# joystick_if.net
KiCad netlist of a schematic drawn in Altium Designer
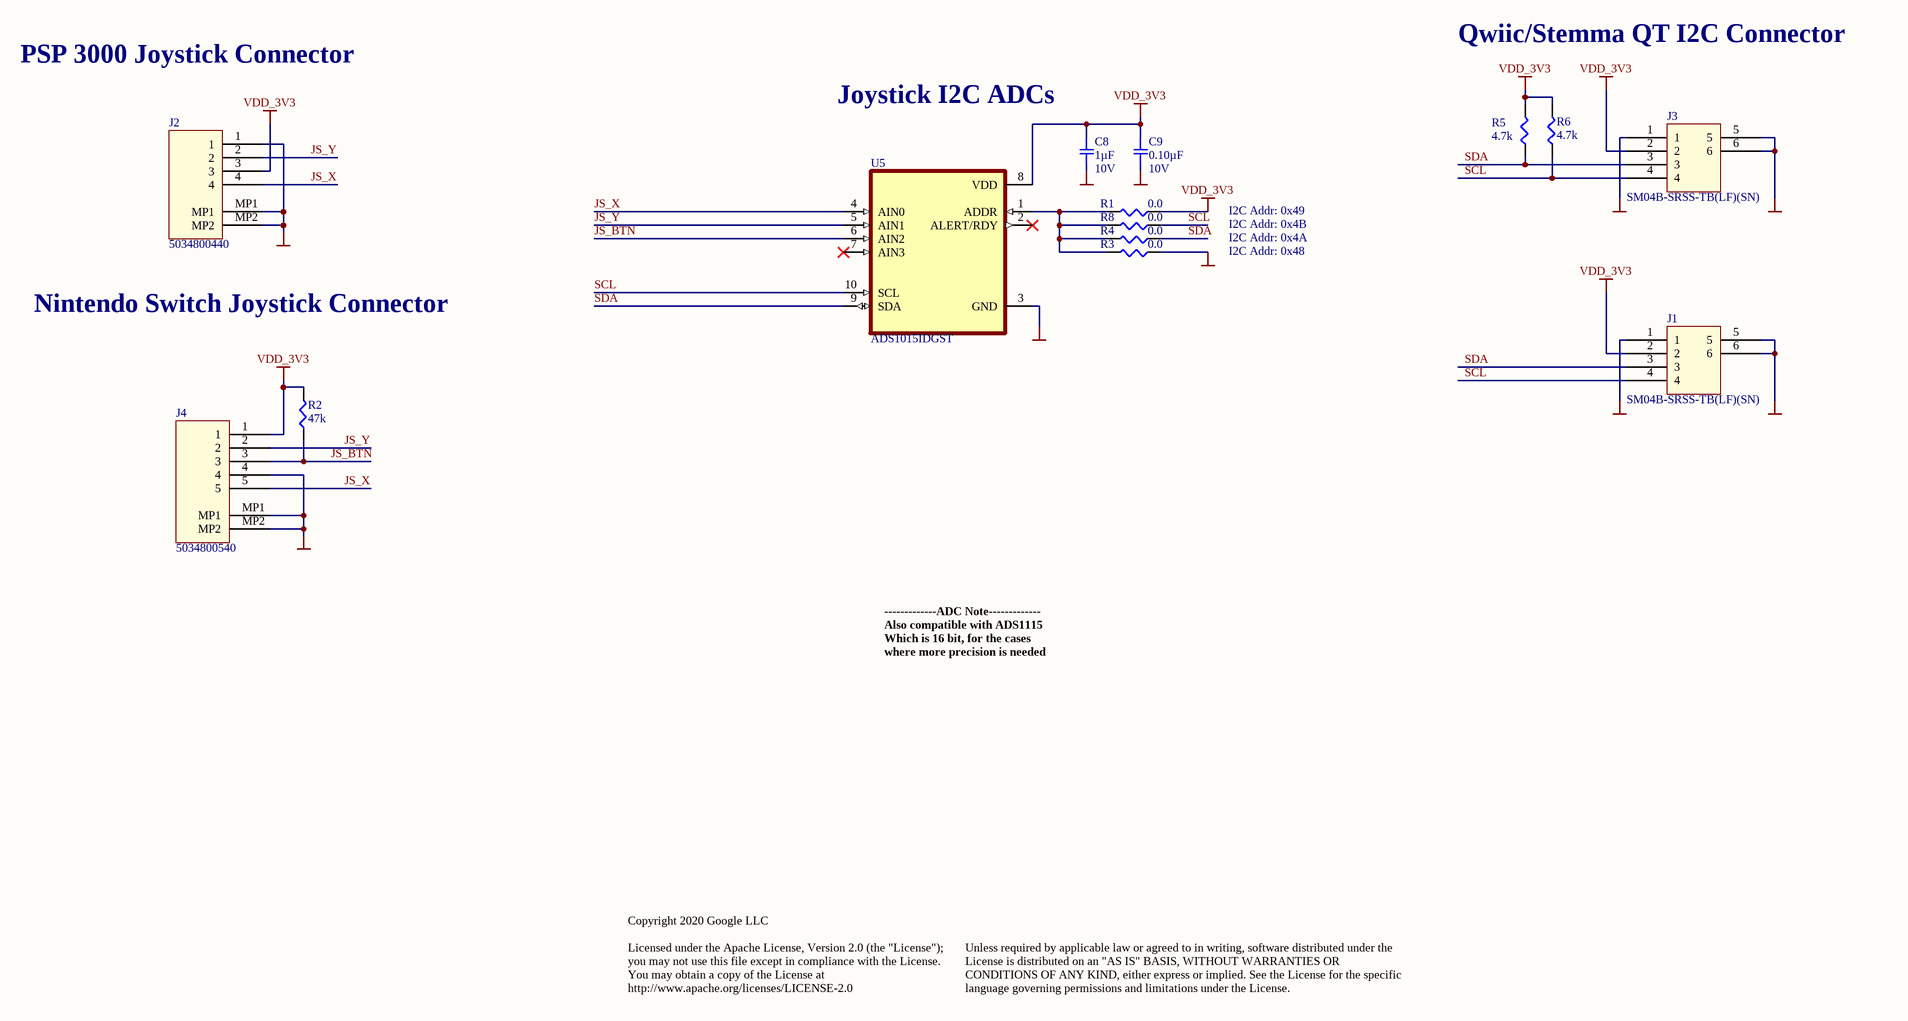
[diagram p0: joystick_if.SchDoc]

(export (version "E")
  (design (tool "Eeschema 10.0.6"))
  (components
    (comp (ref "C8")
      (value "1µF")
      (footprint "SMD-0402C")
      (description "CAP CER 1UF 10V X5R 0402")
      (fields
        (field (name "DIGI-KEY PART NUMBER") "490-3890-1-ND")
        (field (name "PART NUMBER") "GRM155R61A105KE15D")
        (field (name "VOLTAGE") "10V")
      )
      (libsource (lib "cap_murata_0402") (part "GRM155R61A105KE15D"))
    )
    (comp (ref "C9")
      (value "0.10µF")
      (footprint "SMD-0402C")
      (description "CAP CER 0.1UF 10V X5R 0402")
      (fields
        (field (name "DIGI-KEY PART NUMBER") "490-10008-1-ND")
        (field (name "PART NUMBER") "GRM152R61A104KE19D")
        (field (name "VOLTAGE") "10V")
      )
      (libsource (lib "cap_murata_0402") (part "GRM152R61A104KE19D"))
    )
    (comp (ref "J1")
      (value "SM04B-SRSS-TB(LF)(SN)")
      (footprint "JST-SH:4208")
      (libsource (lib "JST-SH") (part "4208"))
    )
    (comp (ref "J2")
      (value "5034800440")
      (footprint "conn_fpc_molex:5034800440")
      (libsource (lib "conn_fpc_molex") (part "5034800440"))
    )
    (comp (ref "J3")
      (value "SM04B-SRSS-TB(LF)(SN)")
      (footprint "JST-SH:4208")
      (libsource (lib "JST-SH") (part "4208"))
    )
    (comp (ref "J4")
      (value "5034800540")
      (footprint "conn_fpc_molex:5034800540")
      (libsource (lib "conn_fpc_molex") (part "5034800540"))
    )
    (comp (ref "R1")
      (value "0.0")
      (footprint "SMD-0402-RES")
      (description "RES SMD 0.0OHM JUMPER 1/10W 0402")
      (fields (field (name "PART NUMBER") "ERJ-2GE0R00X") (field (name "DIGI-KEY PART NUMBER") "P0.0JCT-ND"))
      (libsource (lib "res_0402_panasonic_ERJ") (part "ERJ-2GE0R00X"))
    )
    (comp (ref "R2")
      (value "47k")
      (footprint "SMD-0402-RES")
      (description "RES SMD 47K OHM 5% 1/10W 0402")
      (fields (field (name "PART NUMBER") "ERJ-2GEJ473X") (field (name "DIGI-KEY PART NUMBER") "P47KJCT-ND"))
      (libsource (lib "res_0402_panasonic_ERJ") (part "ERJ-2GEJ473X"))
    )
    (comp (ref "R3")
      (value "0.0")
      (footprint "SMD-0402-RES")
      (description "RES SMD 0.0OHM JUMPER 1/10W 0402")
      (fields (field (name "PART NUMBER") "ERJ-2GE0R00X") (field (name "DIGI-KEY PART NUMBER") "P0.0JCT-ND"))
      (libsource (lib "res_0402_panasonic_ERJ") (part "ERJ-2GE0R00X"))
    )
    (comp (ref "R4")
      (value "0.0")
      (footprint "SMD-0402-RES")
      (description "RES SMD 0.0OHM JUMPER 1/10W 0402")
      (fields (field (name "PART NUMBER") "ERJ-2GE0R00X") (field (name "DIGI-KEY PART NUMBER") "P0.0JCT-ND"))
      (libsource (lib "res_0402_panasonic_ERJ") (part "ERJ-2GE0R00X"))
    )
    (comp (ref "R5")
      (value "4.7k")
      (footprint "SMD-0402-RES")
      (description "RES SMD 4.7K OHM 5% 1/10W 0402")
      (fields (field (name "PART NUMBER") "ERJ-2GEJ472X") (field (name "DIGI-KEY PART NUMBER") "P4.7KJCT-ND"))
      (libsource (lib "res_0402_panasonic_ERJ") (part "ERJ-2GEJ472X"))
    )
    (comp (ref "R6")
      (value "4.7k")
      (footprint "SMD-0402-RES")
      (description "RES SMD 4.7K OHM 5% 1/10W 0402")
      (fields (field (name "PART NUMBER") "ERJ-2GEJ472X") (field (name "DIGI-KEY PART NUMBER") "P4.7KJCT-ND"))
      (libsource (lib "res_0402_panasonic_ERJ") (part "ERJ-2GEJ472X"))
    )
    (comp (ref "R8")
      (value "0.0")
      (footprint "SMD-0402-RES")
      (description "RES SMD 0.0OHM JUMPER 1/10W 0402")
      (fields (field (name "PART NUMBER") "ERJ-2GE0R00X") (field (name "DIGI-KEY PART NUMBER") "P0.0JCT-ND"))
      (libsource (lib "res_0402_panasonic_ERJ") (part "ERJ-2GE0R00X"))
    )
    (comp (ref "U5")
      (value "ADS1015IDGST")
      (footprint "SOP50P490X110-10N:SOP50P490X110-10N")
      (fields (field (name "MF") "Texas Instruments"))
      (libsource (lib "ADS1015IDGST") (part "ADS1015IDGST"))
    )
  )
  (nets
    (net (code "1") (name "/JS_BTN") (class "Default")
      (node (ref "J4") (pin "3") (pinfunction "3_3") (pintype "passive"))
      (node (ref "R2") (pin "1") (pinfunction "1_1") (pintype "passive"))
      (node (ref "U5") (pin "6") (pinfunction "AIN2_6") (pintype "input"))
    )
    (net (code "2") (name "/JS_X") (class "Default")
      (node (ref "J2") (pin "4") (pinfunction "4_4") (pintype "passive"))
      (node (ref "J4") (pin "5") (pinfunction "5_5") (pintype "passive"))
      (node (ref "U5") (pin "4") (pinfunction "AIN0_4") (pintype "input"))
    )
    (net (code "3") (name "/JS_Y") (class "Default")
      (node (ref "J2") (pin "2") (pinfunction "2_2") (pintype "passive"))
      (node (ref "J4") (pin "2") (pinfunction "2_2") (pintype "passive"))
      (node (ref "U5") (pin "5") (pinfunction "AIN1_5") (pintype "input"))
    )
    (net (code "4") (name "/SCL") (class "Default")
      (node (ref "J1") (pin "4") (pinfunction "4_4") (pintype "passive"))
      (node (ref "J3") (pin "4") (pinfunction "4_4") (pintype "passive"))
      (node (ref "R6") (pin "1") (pinfunction "1_1") (pintype "passive"))
      (node (ref "R8") (pin "1") (pinfunction "1_1") (pintype "passive"))
      (node (ref "U5") (pin "10") (pinfunction "SCL_10") (pintype "input"))
    )
    (net (code "5") (name "/SDA") (class "Default")
      (node (ref "J1") (pin "3") (pinfunction "3_3") (pintype "passive"))
      (node (ref "J3") (pin "3") (pinfunction "3_3") (pintype "passive"))
      (node (ref "R4") (pin "1") (pinfunction "1_1") (pintype "passive"))
      (node (ref "R5") (pin "1") (pinfunction "1_1") (pintype "passive"))
      (node (ref "U5") (pin "9") (pinfunction "SDA_9") (pintype "bidirectional"))
    )
    (net (code "6") (name "GND") (class "Default")
      (node (ref "C8") (pin "2") (pinfunction "2_2") (pintype "passive"))
      (node (ref "C9") (pin "2") (pinfunction "2_2") (pintype "passive"))
      (node (ref "J1") (pin "1") (pinfunction "1_1") (pintype "passive"))
      (node (ref "J1") (pin "5") (pinfunction "5_5") (pintype "passive"))
      (node (ref "J1") (pin "6") (pinfunction "6_6") (pintype "passive"))
      (node (ref "J2") (pin "1") (pinfunction "1_1") (pintype "passive"))
      (node (ref "J2") (pin "MP1") (pinfunction "MP1_MP1") (pintype "passive"))
      (node (ref "J2") (pin "MP2") (pinfunction "MP2_MP2") (pintype "passive"))
      (node (ref "J3") (pin "1") (pinfunction "1_1") (pintype "passive"))
      (node (ref "J3") (pin "5") (pinfunction "5_5") (pintype "passive"))
      (node (ref "J3") (pin "6") (pinfunction "6_6") (pintype "passive"))
      (node (ref "J4") (pin "4") (pinfunction "4_4") (pintype "passive"))
      (node (ref "J4") (pin "MP1") (pinfunction "MP1_MP1") (pintype "passive"))
      (node (ref "J4") (pin "MP2") (pinfunction "MP2_MP2") (pintype "passive"))
      (node (ref "R3") (pin "1") (pinfunction "1_1") (pintype "passive"))
      (node (ref "U5") (pin "3") (pinfunction "GND_3") (pintype "power_in"))
    )
    (net (code "7") (name "Net-(U5-ADDR)") (class "Default")
      (node (ref "R1") (pin "2") (pinfunction "2_2") (pintype "passive"))
      (node (ref "R3") (pin "2") (pinfunction "2_2") (pintype "passive"))
      (node (ref "R4") (pin "2") (pinfunction "2_2") (pintype "passive"))
      (node (ref "R8") (pin "2") (pinfunction "2_2") (pintype "passive"))
      (node (ref "U5") (pin "1") (pinfunction "ADDR_1") (pintype "input"))
    )
    (net (code "8") (name "VDD_3V3") (class "Default")
      (node (ref "C8") (pin "1") (pinfunction "1_1") (pintype "passive"))
      (node (ref "C9") (pin "1") (pinfunction "1_1") (pintype "passive"))
      (node (ref "J1") (pin "2") (pinfunction "2_2") (pintype "passive"))
      (node (ref "J2") (pin "3") (pinfunction "3_3") (pintype "passive"))
      (node (ref "J3") (pin "2") (pinfunction "2_2") (pintype "passive"))
      (node (ref "J4") (pin "1") (pinfunction "1_1") (pintype "passive"))
      (node (ref "R1") (pin "1") (pinfunction "1_1") (pintype "passive"))
      (node (ref "R2") (pin "2") (pinfunction "2_2") (pintype "passive"))
      (node (ref "R5") (pin "2") (pinfunction "2_2") (pintype "passive"))
      (node (ref "R6") (pin "2") (pinfunction "2_2") (pintype "passive"))
      (node (ref "U5") (pin "8") (pinfunction "VDD_8") (pintype "power_in"))
    )
    (net (code "9") (name "unconnected-(U5-AIN3-Pad7)") (class "Default")
      (node (ref "U5") (pin "7") (pinfunction "AIN3_7") (pintype "input+no_connect"))
    )
    (net (code "10") (name "unconnected-(U5-ALERT{slash}RDY-Pad2)") (class "Default")
      (node (ref "U5") (pin "2") (pinfunction "ALERT/RDY_2") (pintype "output+no_connect"))
    )
  )
)
